# MB1-LED_BUTTON.net
KiCad netlist of a schematic drawn in Altium Designer
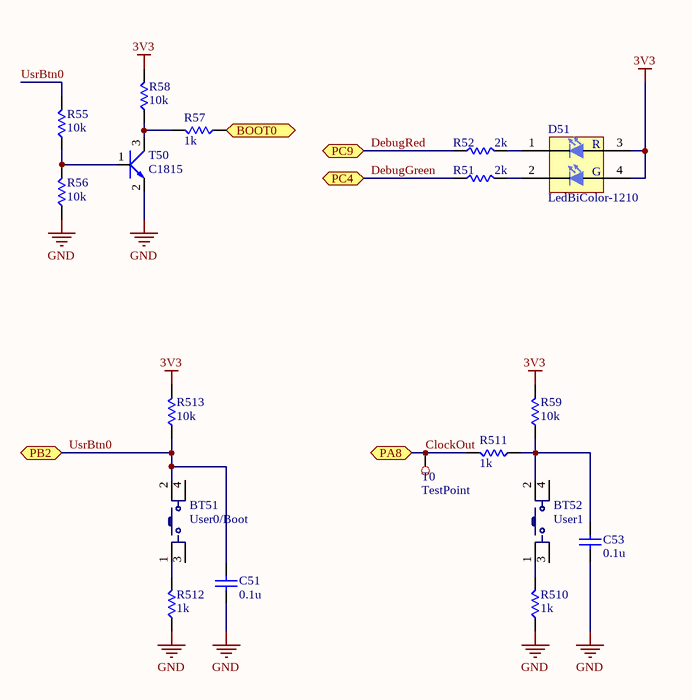
[diagram p0: MB1-LED_BUTTON.SchDoc]

(export (version "E")
  (design (tool "Eeschema 10.0.6"))
  (components
    (comp (ref "BT51")
      (value "User0/Boot")
      (footprint "Horizon_SW_4pin_rectangular")
      (description "Tact switch")
      (libsource (lib "SMD_tact_sw") (part "Button"))
    )
    (comp (ref "BT52")
      (value "User1")
      (footprint "Horizon_SW_4pin_rectangular")
      (description "Tact switch")
      (libsource (lib "SMD_tact_sw") (part "Button"))
    )
    (comp (ref "C51")
      (value "0.1u")
      (footprint "SM_0805_LD")
      (description "Non-polarity ceramic capacitor")
      (fields (field (name "Comment") "CAP_Ceramic") (field (name "PUBLISHER") "Altium Limited"))
      (libsource (lib "Copy of HLib_device_library") (part "C_Ceramic"))
    )
    (comp (ref "C53")
      (value "0.1u")
      (footprint "SM_0805_LD")
      (description "Non-polarity ceramic capacitor")
      (fields (field (name "Comment") "CAP_Ceramic") (field (name "PUBLISHER") "Altium Limited"))
      (libsource (lib "Copy of HLib_device_library") (part "C_Ceramic"))
    )
    (comp (ref "D51")
      (value "LedBiColor-1210")
      (footprint "Led-BiColor")
      (libsource (lib "MyLib") (part "LedBiColor-1210"))
    )
    (comp (ref "R51")
      (value "2k")
      (footprint "SM_0805_LD")
      (description "Resistor")
      (fields (field (name "PUBLISHER") "Altium Limited"))
      (libsource (lib "Copy of HLib_device_library") (part "R"))
    )
    (comp (ref "R52")
      (value "2k")
      (footprint "SM_0805_LD")
      (description "Resistor")
      (fields (field (name "PUBLISHER") "Altium Limited"))
      (libsource (lib "Copy of HLib_device_library") (part "R"))
    )
    (comp (ref "R55")
      (value "10k")
      (footprint "SM_0805_LD")
      (description "Resistor")
      (fields (field (name "PUBLISHER") "Altium Limited"))
      (libsource (lib "Copy of HLib_device_library") (part "R"))
    )
    (comp (ref "R56")
      (value "10k")
      (footprint "SM_0805_LD")
      (description "Resistor")
      (fields (field (name "PUBLISHER") "Altium Limited"))
      (libsource (lib "Copy of HLib_device_library") (part "R"))
    )
    (comp (ref "R57")
      (value "1k")
      (footprint "SM_0805_LD")
      (description "Resistor")
      (fields (field (name "PUBLISHER") "Altium Limited"))
      (libsource (lib "Copy of HLib_device_library") (part "R"))
    )
    (comp (ref "R58")
      (value "10k")
      (footprint "SM_0805_LD")
      (description "Resistor")
      (fields (field (name "PUBLISHER") "Altium Limited"))
      (libsource (lib "Copy of HLib_device_library") (part "R"))
    )
    (comp (ref "R59")
      (value "10k")
      (footprint "SM_0805_LD")
      (description "Resistor")
      (fields (field (name "PUBLISHER") "Altium Limited"))
      (libsource (lib "Copy of HLib_device_library") (part "R"))
    )
    (comp (ref "R510")
      (value "1k")
      (footprint "SM_0805_LD")
      (description "Resistor")
      (fields (field (name "PUBLISHER") "Altium Limited"))
      (libsource (lib "Copy of HLib_device_library") (part "R"))
    )
    (comp (ref "R511")
      (value "1k")
      (footprint "SM_0805_LD")
      (description "Resistor")
      (fields (field (name "PUBLISHER") "Altium Limited"))
      (libsource (lib "Copy of HLib_device_library") (part "R"))
    )
    (comp (ref "R512")
      (value "1k")
      (footprint "SM_0805_LD")
      (description "Resistor")
      (fields (field (name "PUBLISHER") "Altium Limited"))
      (libsource (lib "Copy of HLib_device_library") (part "R"))
    )
    (comp (ref "R513")
      (value "10k")
      (footprint "SM_0805_LD")
      (description "Resistor")
      (fields (field (name "PUBLISHER") "Altium Limited"))
      (libsource (lib "Copy of HLib_device_library") (part "R"))
    )
    (comp (ref "T0") (value "TestPoint") (footprint "TestPoint") (libsource (lib "MyLib") (part "TestPoint")))
    (comp (ref "T50") (value "C1815") (footprint "SOT23") (libsource (lib "MyLib") (part "C1815")))
  )
  (nets
    (net (code "1") (name "/BOOT0") (class "Default")
      (node (ref "R57") (pin "1") (pinfunction "1_1") (pintype "passive"))
    )
    (net (code "2") (name "/ClockOut") (class "Default")
      (node (ref "R511") (pin "2") (pinfunction "2_2") (pintype "passive"))
      (node (ref "T0") (pin "1") (pinfunction "0_1") (pintype "passive"))
    )
    (net (code "3") (name "/DebugGreen") (class "Default")
      (node (ref "R51") (pin "1") (pinfunction "1_1") (pintype "passive"))
    )
    (net (code "4") (name "/DebugRed") (class "Default")
      (node (ref "R52") (pin "1") (pinfunction "1_1") (pintype "passive"))
    )
    (net (code "5") (name "/UsrBtn0") (class "Default")
      (node (ref "BT51") (pin "2") (pintype "passive"))
      (node (ref "C51") (pin "2") (pinfunction "2_2") (pintype "passive"))
      (node (ref "R513") (pin "1") (pinfunction "1_1") (pintype "passive"))
      (node (ref "R55") (pin "2") (pinfunction "2_2") (pintype "passive"))
    )
    (net (code "6") (name "3V3") (class "Default")
      (node (ref "D51") (pin "3") (pinfunction "R+_3") (pintype "passive"))
      (node (ref "D51") (pin "4") (pinfunction "G+_4") (pintype "passive"))
      (node (ref "R513") (pin "2") (pinfunction "2_2") (pintype "passive"))
      (node (ref "R58") (pin "2") (pinfunction "2_2") (pintype "passive"))
      (node (ref "R59") (pin "2") (pinfunction "2_2") (pintype "passive"))
    )
    (net (code "7") (name "GND") (class "Default")
      (node (ref "C51") (pin "1") (pinfunction "1_1") (pintype "passive"))
      (node (ref "C53") (pin "1") (pinfunction "1_1") (pintype "passive"))
      (node (ref "R510") (pin "1") (pinfunction "1_1") (pintype "passive"))
      (node (ref "R512") (pin "1") (pinfunction "1_1") (pintype "passive"))
      (node (ref "R56") (pin "1") (pinfunction "1_1") (pintype "passive"))
      (node (ref "T50") (pin "2") (pinfunction "E_2") (pintype "passive"))
    )
    (net (code "8") (name "Net-(BT51-Pad1)") (class "Default")
      (node (ref "BT51") (pin "1") (pintype "passive"))
      (node (ref "R512") (pin "2") (pinfunction "2_2") (pintype "passive"))
    )
    (net (code "9") (name "Net-(BT52-Pad1)") (class "Default")
      (node (ref "BT52") (pin "1") (pintype "passive"))
      (node (ref "R510") (pin "2") (pinfunction "2_2") (pintype "passive"))
    )
    (net (code "10") (name "Net-(BT52-Pad2)") (class "Default")
      (node (ref "BT52") (pin "2") (pintype "passive"))
      (node (ref "C53") (pin "2") (pinfunction "2_2") (pintype "passive"))
      (node (ref "R511") (pin "1") (pinfunction "1_1") (pintype "passive"))
      (node (ref "R59") (pin "1") (pinfunction "1_1") (pintype "passive"))
    )
    (net (code "11") (name "Net-(D51-G-)") (class "Default")
      (node (ref "D51") (pin "2") (pinfunction "G-_2") (pintype "passive"))
      (node (ref "R51") (pin "2") (pinfunction "2_2") (pintype "passive"))
    )
    (net (code "12") (name "Net-(D51-R-)") (class "Default")
      (node (ref "D51") (pin "1") (pinfunction "R-_1") (pintype "passive"))
      (node (ref "R52") (pin "2") (pinfunction "2_2") (pintype "passive"))
    )
    (net (code "13") (name "Net-(T50-B)") (class "Default")
      (node (ref "R55") (pin "1") (pinfunction "1_1") (pintype "passive"))
      (node (ref "R56") (pin "2") (pinfunction "2_2") (pintype "passive"))
      (node (ref "T50") (pin "1") (pinfunction "B_1") (pintype "passive"))
    )
    (net (code "14") (name "Net-(T50-C)") (class "Default")
      (node (ref "R57") (pin "2") (pinfunction "2_2") (pintype "passive"))
      (node (ref "R58") (pin "1") (pinfunction "1_1") (pintype "passive"))
      (node (ref "T50") (pin "3") (pinfunction "C_3") (pintype "passive"))
    )
    (net (code "15") (name "unconnected-(BT51-Pad3)") (class "Default")
      (node (ref "BT51") (pin "3") (pintype "passive"))
    )
    (net (code "16") (name "unconnected-(BT51-Pad4)") (class "Default")
      (node (ref "BT51") (pin "4") (pintype "passive"))
    )
    (net (code "17") (name "unconnected-(BT52-Pad3)") (class "Default")
      (node (ref "BT52") (pin "3") (pintype "passive"))
    )
    (net (code "18") (name "unconnected-(BT52-Pad4)") (class "Default")
      (node (ref "BT52") (pin "4") (pintype "passive"))
    )
  )
)
